# cOMBO.net
KiCad netlist of a schematic drawn in Altium Designer
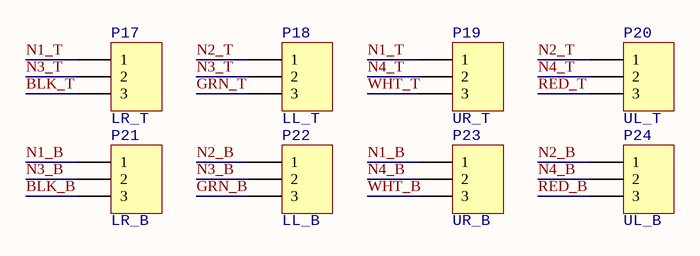
[diagram p0: cOMBO.SchDoc]

(export (version "E")
  (design (tool "Eeschema 10.0.6"))
  (components
    (comp (ref "P17")
      (value "LR_T")
      (footprint "HDR1X3")
      (description "Header, 3-Pin")
      (fields (field (name "PUBLISHER") "Altium Limited"))
      (libsource (lib "Miscellaneous Connectors") (part "Header 3"))
    )
    (comp (ref "P18")
      (value "LL_T")
      (footprint "HDR1X3")
      (description "Header, 3-Pin")
      (fields (field (name "PUBLISHER") "Altium Limited"))
      (libsource (lib "Miscellaneous Connectors") (part "Header 3"))
    )
    (comp (ref "P19")
      (value "UR_T")
      (footprint "HDR1X3")
      (description "Header, 3-Pin")
      (fields (field (name "PUBLISHER") "Altium Limited"))
      (libsource (lib "Miscellaneous Connectors") (part "Header 3"))
    )
    (comp (ref "P20")
      (value "UL_T")
      (footprint "HDR1X3")
      (description "Header, 3-Pin")
      (fields (field (name "PUBLISHER") "Altium Limited"))
      (libsource (lib "Miscellaneous Connectors") (part "Header 3"))
    )
    (comp (ref "P21")
      (value "LR_B")
      (footprint "HDR1X3")
      (description "Header, 3-Pin")
      (fields (field (name "PUBLISHER") "Altium Limited"))
      (libsource (lib "Miscellaneous Connectors") (part "Header 3"))
    )
    (comp (ref "P22")
      (value "LL_B")
      (footprint "HDR1X3")
      (description "Header, 3-Pin")
      (fields (field (name "PUBLISHER") "Altium Limited"))
      (libsource (lib "Miscellaneous Connectors") (part "Header 3"))
    )
    (comp (ref "P23")
      (value "UR_B")
      (footprint "HDR1X3")
      (description "Header, 3-Pin")
      (fields (field (name "PUBLISHER") "Altium Limited"))
      (libsource (lib "Miscellaneous Connectors") (part "Header 3"))
    )
    (comp (ref "P24")
      (value "UL_B")
      (footprint "HDR1X3")
      (description "Header, 3-Pin")
      (fields (field (name "PUBLISHER") "Altium Limited"))
      (libsource (lib "Miscellaneous Connectors") (part "Header 3"))
    )
  )
  (nets
    (net (code "1") (name "/BLK_B") (class "Default")
      (node (ref "P21") (pin "3") (pinfunction "3_3") (pintype "passive"))
    )
    (net (code "2") (name "/BLK_T") (class "Default")
      (node (ref "P17") (pin "3") (pinfunction "3_3") (pintype "passive"))
    )
    (net (code "3") (name "/GRN_B") (class "Default")
      (node (ref "P22") (pin "3") (pinfunction "3_3") (pintype "passive"))
    )
    (net (code "4") (name "/GRN_T") (class "Default")
      (node (ref "P18") (pin "3") (pinfunction "3_3") (pintype "passive"))
    )
    (net (code "5") (name "/N1_B") (class "Default")
      (node (ref "P21") (pin "1") (pinfunction "1_1") (pintype "passive"))
      (node (ref "P23") (pin "1") (pinfunction "1_1") (pintype "passive"))
    )
    (net (code "6") (name "/N1_T") (class "Default")
      (node (ref "P17") (pin "1") (pinfunction "1_1") (pintype "passive"))
      (node (ref "P19") (pin "1") (pinfunction "1_1") (pintype "passive"))
    )
    (net (code "7") (name "/N2_B") (class "Default")
      (node (ref "P22") (pin "1") (pinfunction "1_1") (pintype "passive"))
      (node (ref "P24") (pin "1") (pinfunction "1_1") (pintype "passive"))
    )
    (net (code "8") (name "/N2_T") (class "Default")
      (node (ref "P18") (pin "1") (pinfunction "1_1") (pintype "passive"))
      (node (ref "P20") (pin "1") (pinfunction "1_1") (pintype "passive"))
    )
    (net (code "9") (name "/N3_B") (class "Default")
      (node (ref "P21") (pin "2") (pinfunction "2_2") (pintype "passive"))
      (node (ref "P22") (pin "2") (pinfunction "2_2") (pintype "passive"))
    )
    (net (code "10") (name "/N3_T") (class "Default")
      (node (ref "P17") (pin "2") (pinfunction "2_2") (pintype "passive"))
      (node (ref "P18") (pin "2") (pinfunction "2_2") (pintype "passive"))
    )
    (net (code "11") (name "/N4_B") (class "Default")
      (node (ref "P23") (pin "2") (pinfunction "2_2") (pintype "passive"))
      (node (ref "P24") (pin "2") (pinfunction "2_2") (pintype "passive"))
    )
    (net (code "12") (name "/N4_T") (class "Default")
      (node (ref "P19") (pin "2") (pinfunction "2_2") (pintype "passive"))
      (node (ref "P20") (pin "2") (pinfunction "2_2") (pintype "passive"))
    )
    (net (code "13") (name "/RED_B") (class "Default")
      (node (ref "P24") (pin "3") (pinfunction "3_3") (pintype "passive"))
    )
    (net (code "14") (name "/RED_T") (class "Default")
      (node (ref "P20") (pin "3") (pinfunction "3_3") (pintype "passive"))
    )
    (net (code "15") (name "/WHT_B") (class "Default")
      (node (ref "P23") (pin "3") (pinfunction "3_3") (pintype "passive"))
    )
    (net (code "16") (name "/WHT_T") (class "Default")
      (node (ref "P19") (pin "3") (pinfunction "3_3") (pintype "passive"))
    )
  )
)
